# ATmega128RFA1-DevBoard.net
KiCad netlist of a schematic drawn in EAGLE
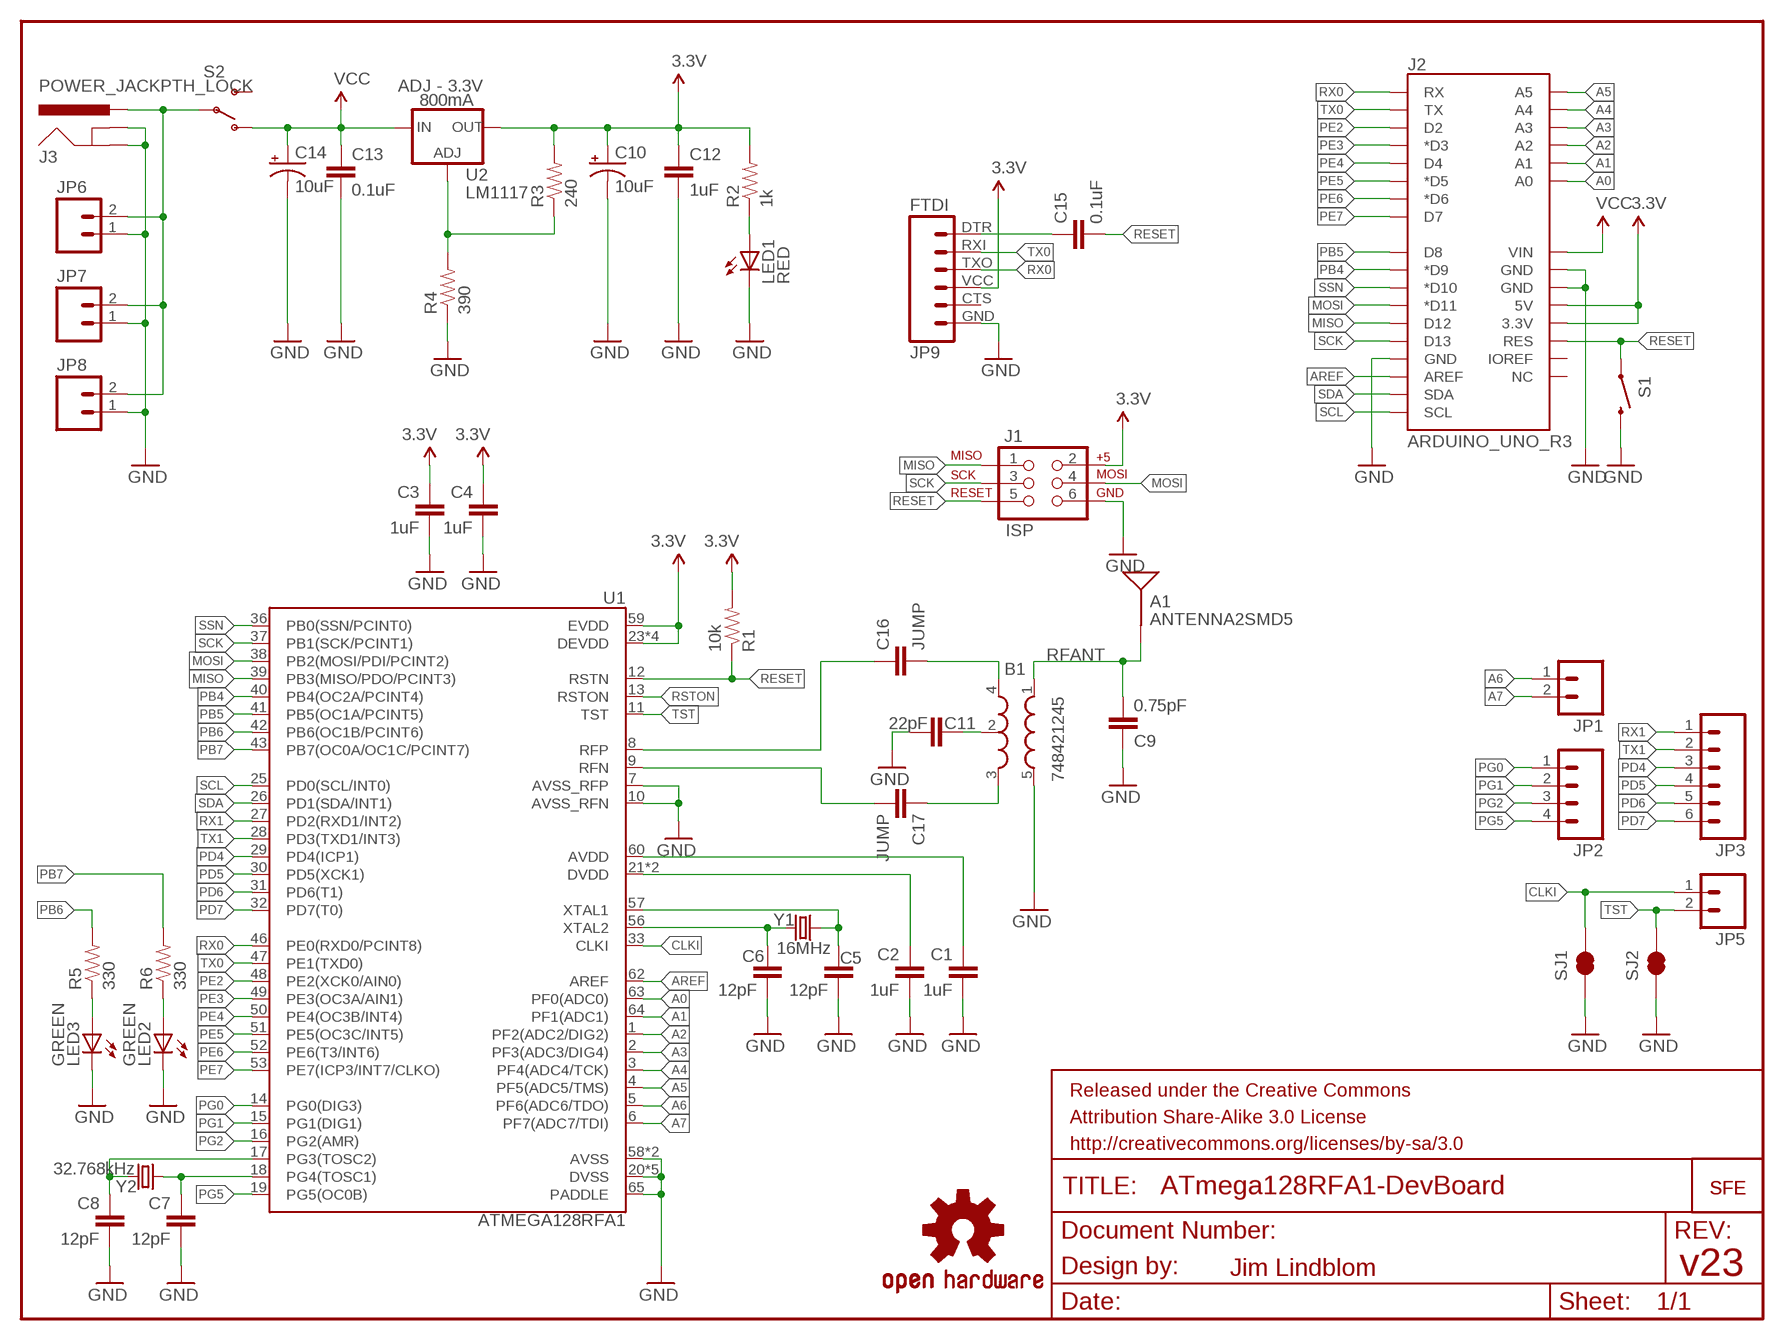
[diagram p0: schematic, sheet 1]

(export (version "E")
  (design (tool "Eeschema 10.0.6"))
  (components
    (comp (ref "A1")
      (value "ANTENNA2SMD5")
      (footprint "eagle-import:ANTENNA-CHIP5")
      (libsource (lib "eagle-import") (part "ANTENNA2SMD5"))
    )
    (comp (ref "B1")
      (value "748421245")
      (footprint "eagle-import:BALUN")
      (libsource (lib "eagle-import") (part "BALUN0805"))
    )
    (comp (ref "C1")
      (value "1uF")
      (footprint "eagle-import:0402-CAP")
      (libsource (lib "eagle-import") (part "SparkFun-Passives_CAP0402-CAP"))
    )
    (comp (ref "C2")
      (value "1uF")
      (footprint "eagle-import:0402-CAP")
      (libsource (lib "eagle-import") (part "SparkFun-Passives_CAP0402-CAP"))
    )
    (comp (ref "C3")
      (value "1uF")
      (footprint "eagle-import:0402-CAP")
      (libsource (lib "eagle-import") (part "SparkFun-Passives_CAP0402-CAP"))
    )
    (comp (ref "C4")
      (value "1uF")
      (footprint "eagle-import:0402-CAP")
      (libsource (lib "eagle-import") (part "SparkFun-Passives_CAP0402-CAP"))
    )
    (comp (ref "C5")
      (value "12pF")
      (footprint "eagle-import:0402-CAP")
      (libsource (lib "eagle-import") (part "SparkFun-Passives_CAP0402-CAP"))
    )
    (comp (ref "C6")
      (value "12pF")
      (footprint "eagle-import:0402-CAP")
      (libsource (lib "eagle-import") (part "SparkFun-Passives_CAP0402-CAP"))
    )
    (comp (ref "C7")
      (value "12pF")
      (footprint "eagle-import:0402-CAP")
      (libsource (lib "eagle-import") (part "SparkFun-Passives_CAP0402-CAP"))
    )
    (comp (ref "C8")
      (value "12pF")
      (footprint "eagle-import:0402-CAP")
      (libsource (lib "eagle-import") (part "SparkFun-Passives_CAP0402-CAP"))
    )
    (comp (ref "C9")
      (value "0.75pF")
      (footprint "eagle-import:0402-CAP")
      (libsource (lib "eagle-import") (part "SparkFun-Passives_CAP0402-CAP"))
    )
    (comp (ref "C10")
      (value "10uF")
      (footprint "eagle-import:EIA3216")
      (libsource (lib "eagle-import") (part "CAP_POL1206"))
    )
    (comp (ref "C11")
      (value "22pF")
      (footprint "eagle-import:0402-CAP")
      (libsource (lib "eagle-import") (part "SparkFun-Passives_CAP0402-CAP"))
    )
    (comp (ref "C12")
      (value "1uF")
      (footprint "eagle-import:0402-CAP")
      (libsource (lib "eagle-import") (part "SparkFun-Passives_CAP0402-CAP"))
    )
    (comp (ref "C13")
      (value "0.1uF")
      (footprint "eagle-import:0402-CAP")
      (libsource (lib "eagle-import") (part "SparkFun-Passives_CAP0402-CAP"))
    )
    (comp (ref "C14")
      (value "10uF")
      (footprint "eagle-import:EIA3216")
      (libsource (lib "eagle-import") (part "CAP_POL1206"))
    )
    (comp (ref "C15")
      (value "0.1uF")
      (footprint "eagle-import:0402-CAP")
      (libsource (lib "eagle-import") (part "SparkFun-Passives_CAP0402-CAP"))
    )
    (comp (ref "C16")
      (value "JUMP")
      (footprint "eagle-import:0402-CAP")
      (libsource (lib "eagle-import") (part "CAP0402-CAP"))
    )
    (comp (ref "C17")
      (value "JUMP")
      (footprint "eagle-import:0402-CAP")
      (libsource (lib "eagle-import") (part "CAP0402-CAP"))
    )
    (comp (ref "J1")
      (value "ISP")
      (footprint "eagle-import:2X3-NS")
      (libsource (lib "eagle-import") (part "AVR_SPI_PRG_6NS"))
    )
    (comp (ref "J2")
      (value "ARDUINO_UNO_R3")
      (footprint "eagle-import:ARDUINO_UNO_R3")
      (libsource (lib "eagle-import") (part "ARDUINO_UNO_R3"))
    )
    (comp (ref "J3")
      (value "POWER_JACKPTH_LOCK")
      (footprint "eagle-import:POWER_JACK_PTH_LOCK")
      (libsource (lib "eagle-import") (part "POWER_JACKPTH_LOCK"))
    )
    (comp (ref "JP1")
      (value "M021X02_NO_SILK")
      (footprint "eagle-import:1X02_NO_SILK")
      (libsource (lib "eagle-import") (part "M021X02_NO_SILK"))
    )
    (comp (ref "JP2")
      (value "M041X04_NO_SILK")
      (footprint "eagle-import:1X04_NO_SILK")
      (libsource (lib "eagle-import") (part "M041X04_NO_SILK"))
    )
    (comp (ref "JP3")
      (value "M06SIP-NS")
      (footprint "eagle-import:1X06_NS")
      (libsource (lib "eagle-import") (part "M06SIP-NS"))
    )
    (comp (ref "JP4")
      (value "LOGO-SFENEW")
      (footprint "eagle-import:SFE-NEW-WEBLOGO")
      (libsource (lib "eagle-import") (part "LOGO-SFENEW"))
    )
    (comp (ref "JP5")
      (value "M021X02_NO_SILK")
      (footprint "eagle-import:1X02_NO_SILK")
      (libsource (lib "eagle-import") (part "M021X02_NO_SILK"))
    )
    (comp (ref "JP6")
      (value "M02JST-PTH-2")
      (footprint "eagle-import:JST-2-PTH")
      (libsource (lib "eagle-import") (part "M02JST-PTH-2"))
    )
    (comp (ref "JP7")
      (value "M021X02_NO_SILK")
      (footprint "eagle-import:1X02_NO_SILK")
      (libsource (lib "eagle-import") (part "M021X02_NO_SILK"))
    )
    (comp (ref "JP8")
      (value "M023.5MM-NO_SILK")
      (footprint "eagle-import:SCREWTERMINAL-3.5MM-2-NS")
      (libsource (lib "eagle-import") (part "M023.5MM-NO_SILK"))
    )
    (comp (ref "JP9")
      (value "FTDI")
      (footprint "eagle-import:FTDI_BASIC")
      (libsource (lib "eagle-import") (part "FTDI_BASICPTH"))
    )
    (comp (ref "JP10")
      (value "LOGO-SFENEW")
      (footprint "eagle-import:SFE-NEW-WEBLOGO")
      (libsource (lib "eagle-import") (part "LOGO-SFENEW"))
    )
    (comp (ref "LED1")
      (value "RED")
      (footprint "eagle-import:LED-0603")
      (libsource (lib "eagle-import") (part "LED0603"))
    )
    (comp (ref "LED2")
      (value "GREEN")
      (footprint "eagle-import:LED-0603")
      (libsource (lib "eagle-import") (part "LED0603"))
    )
    (comp (ref "LED3")
      (value "GREEN")
      (footprint "eagle-import:LED-0603")
      (libsource (lib "eagle-import") (part "LED0603"))
    )
    (comp (ref "R1")
      (value "10k")
      (footprint "eagle-import:0402-RES")
      (libsource (lib "eagle-import") (part "SparkFun-Passives_RESISTOR0402-RES"))
    )
    (comp (ref "R2")
      (value "1k")
      (footprint "eagle-import:0402-RES")
      (libsource (lib "eagle-import") (part "SparkFun-Passives_RESISTOR0402-RES"))
    )
    (comp (ref "R3")
      (value "240")
      (footprint "eagle-import:0402-RES")
      (libsource (lib "eagle-import") (part "RESISTOR0402-RES"))
    )
    (comp (ref "R4")
      (value "390")
      (footprint "eagle-import:0402-RES")
      (libsource (lib "eagle-import") (part "RESISTOR0402-RES"))
    )
    (comp (ref "R5")
      (value "330")
      (footprint "eagle-import:0402-RES")
      (libsource (lib "eagle-import") (part "RESISTOR0402-RES"))
    )
    (comp (ref "R6")
      (value "330")
      (footprint "eagle-import:0402-RES")
      (libsource (lib "eagle-import") (part "RESISTOR0402-RES"))
    )
    (comp (ref "S1")
      (value "SWITCH-MOMENTARY-2SMD")
      (footprint "eagle-import:TACTILE_SWITCH_SMD")
      (libsource (lib "eagle-import") (part "SWITCH-MOMENTARY-2SMD"))
    )
    (comp (ref "S2")
      (value "SWITCH-SPST-SMD-A")
      (footprint "eagle-import:SWITCH-SPST-SMD-A")
      (libsource (lib "eagle-import") (part "SWITCH-SPST-SMD-A"))
    )
    (comp (ref "SJ1")
      (value "SOLDERJUMPERTRACE")
      (footprint "eagle-import:SJ_2S-TRACE")
      (libsource (lib "eagle-import") (part "SOLDERJUMPERTRACE"))
    )
    (comp (ref "SJ2")
      (value "SOLDERJUMPERTRACE")
      (footprint "eagle-import:SJ_2S-TRACE")
      (libsource (lib "eagle-import") (part "SOLDERJUMPERTRACE"))
    )
    (comp (ref "U$1")
      (value "OSHW-LOGOS")
      (footprint "eagle-import:OSHW-LOGO-S")
      (libsource (lib "eagle-import") (part "OSHW-LOGOS"))
    )
    (comp (ref "U1")
      (value "ATMEGA128RFA1")
      (footprint "eagle-import:QFN-64")
      (libsource (lib "eagle-import") (part "ATMEGA128RFA1"))
    )
    (comp (ref "U2")
      (value "LM1117")
      (footprint "eagle-import:SOT223")
      (libsource (lib "eagle-import") (part "V_REG_317SMD"))
    )
    (comp (ref "Y1")
      (value "16MHz")
      (footprint "eagle-import:CRYSTAL-SMD-5X3")
      (libsource (lib "eagle-import") (part "CRYSTAL5X3"))
    )
    (comp (ref "Y2")
      (value "32.768kHz")
      (footprint "eagle-import:CRYSTAL-32KHZ-SMD")
      (libsource (lib "eagle-import") (part "CRYSTAL32-SMD"))
    )
  )
  (nets
    (net (code "1") (name "/RFANT") (class "Default")
      (node (ref "A1") (pin "FEED") (pinfunction "SIGNAL_FEED") (pintype "bidirectional"))
      (node (ref "B1") (pin "1") (pinfunction "IN_1") (pintype "bidirectional"))
      (node (ref "C9") (pin "2") (pinfunction "2_2") (pintype "passive"))
    )
    (net (code "2") (name "3.3V") (class "Default")
      (node (ref "C10") (pin "A") (pinfunction "+_A") (pintype "passive"))
      (node (ref "C12") (pin "1") (pinfunction "1_1") (pintype "passive"))
      (node (ref "C3") (pin "1") (pinfunction "1_1") (pintype "passive"))
      (node (ref "C4") (pin "1") (pinfunction "1_1") (pintype "passive"))
      (node (ref "J1") (pin "2") (pinfunction "2_2") (pintype "passive"))
      (node (ref "J2") (pin "3.3V") (pinfunction "3.3V_3.3V") (pintype "bidirectional"))
      (node (ref "J2") (pin "5V") (pinfunction "5V_5V") (pintype "bidirectional"))
      (node (ref "JP9") (pin "VCC") (pinfunction "4_VCC") (pintype "passive"))
      (node (ref "R1") (pin "2") (pinfunction "2_2") (pintype "passive"))
      (node (ref "R2") (pin "2") (pinfunction "2_2") (pintype "passive"))
      (node (ref "R3") (pin "2") (pinfunction "2_2") (pintype "passive"))
      (node (ref "U1") (pin "23") (pinfunction "DEVDD_23") (pintype "bidirectional"))
      (node (ref "U1") (pin "34") (pinfunction "DEVDD_34") (pintype "bidirectional"))
      (node (ref "U1") (pin "44") (pinfunction "DEVDD_44") (pintype "bidirectional"))
      (node (ref "U1") (pin "54") (pinfunction "DEVDD_54") (pintype "bidirectional"))
      (node (ref "U1") (pin "59") (pinfunction "EVDD_59") (pintype "bidirectional"))
      (node (ref "U2") (pin "2") (pinfunction "OUT_2") (pintype "output"))
    )
    (net (code "3") (name "A0") (class "Default")
      (node (ref "J2") (pin "A0") (pinfunction "A0_A0") (pintype "bidirectional"))
      (node (ref "U1") (pin "63") (pinfunction "PF0(ADC0)_63") (pintype "bidirectional"))
    )
    (net (code "4") (name "A1") (class "Default")
      (node (ref "J2") (pin "A1") (pinfunction "A1_A1") (pintype "bidirectional"))
      (node (ref "U1") (pin "64") (pinfunction "PF1(ADC1)_64") (pintype "bidirectional"))
    )
    (net (code "5") (name "A2") (class "Default")
      (node (ref "J2") (pin "A2") (pinfunction "A2_A2") (pintype "bidirectional"))
      (node (ref "U1") (pin "1") (pinfunction "PF2(ADC2/DIG2)_1") (pintype "bidirectional"))
    )
    (net (code "6") (name "A3") (class "Default")
      (node (ref "J2") (pin "A3") (pinfunction "A3_A3") (pintype "bidirectional"))
      (node (ref "U1") (pin "2") (pinfunction "PF3(ADC3/DIG4)_2") (pintype "bidirectional"))
    )
    (net (code "7") (name "A4") (class "Default")
      (node (ref "J2") (pin "A4") (pinfunction "A4_A4") (pintype "bidirectional"))
      (node (ref "U1") (pin "3") (pinfunction "PF4(ADC4/TCK)_3") (pintype "bidirectional"))
    )
    (net (code "8") (name "A5") (class "Default")
      (node (ref "J2") (pin "A5") (pinfunction "A5_A5") (pintype "bidirectional"))
      (node (ref "U1") (pin "4") (pinfunction "PF5(ADC5/TMS)_4") (pintype "bidirectional"))
    )
    (net (code "9") (name "A6") (class "Default")
      (node (ref "JP1") (pin "1") (pinfunction "1_1") (pintype "passive"))
      (node (ref "U1") (pin "5") (pinfunction "PF6(ADC6/TDO)_5") (pintype "bidirectional"))
    )
    (net (code "10") (name "A7") (class "Default")
      (node (ref "JP1") (pin "2") (pinfunction "2_2") (pintype "passive"))
      (node (ref "U1") (pin "6") (pinfunction "PF7(ADC7/TDI)_6") (pintype "bidirectional"))
    )
    (net (code "11") (name "AREF") (class "Default")
      (node (ref "J2") (pin "AREF") (pinfunction "AREF_AREF") (pintype "bidirectional"))
      (node (ref "U1") (pin "62") (pinfunction "AREF_62") (pintype "bidirectional"))
    )
    (net (code "12") (name "CLKI") (class "Default")
      (node (ref "JP5") (pin "1") (pinfunction "1_1") (pintype "passive"))
      (node (ref "SJ1") (pin "2") (pinfunction "2_2") (pintype "passive"))
      (node (ref "U1") (pin "33") (pinfunction "CLKI_33") (pintype "bidirectional"))
    )
    (net (code "13") (name "GND") (class "Default")
      (node (ref "B1") (pin "5") (pinfunction "GND_5") (pintype "bidirectional"))
      (node (ref "C1") (pin "2") (pinfunction "2_2") (pintype "passive"))
      (node (ref "C10") (pin "C") (pinfunction "-_C") (pintype "passive"))
      (node (ref "C11") (pin "2") (pinfunction "2_2") (pintype "passive"))
      (node (ref "C12") (pin "2") (pinfunction "2_2") (pintype "passive"))
      (node (ref "C13") (pin "2") (pinfunction "2_2") (pintype "passive"))
      (node (ref "C14") (pin "C") (pinfunction "-_C") (pintype "passive"))
      (node (ref "C2") (pin "2") (pinfunction "2_2") (pintype "passive"))
      (node (ref "C3") (pin "2") (pinfunction "2_2") (pintype "passive"))
      (node (ref "C4") (pin "2") (pinfunction "2_2") (pintype "passive"))
      (node (ref "C5") (pin "2") (pinfunction "2_2") (pintype "passive"))
      (node (ref "C6") (pin "2") (pinfunction "2_2") (pintype "passive"))
      (node (ref "C7") (pin "2") (pinfunction "2_2") (pintype "passive"))
      (node (ref "C8") (pin "2") (pinfunction "2_2") (pintype "passive"))
      (node (ref "C9") (pin "1") (pinfunction "1_1") (pintype "passive"))
      (node (ref "J1") (pin "6") (pinfunction "6_6") (pintype "passive"))
      (node (ref "J2") (pin "GND@0") (pinfunction "GND_GND@0") (pintype "bidirectional"))
      (node (ref "J2") (pin "GND@1") (pinfunction "GND_GND@1") (pintype "bidirectional"))
      (node (ref "J2") (pin "GND@2") (pinfunction "GND_GND@2") (pintype "bidirectional"))
      (node (ref "J3") (pin "GND") (pinfunction "GND_GND") (pintype "bidirectional"))
      (node (ref "J3") (pin "GNDBREAK") (pinfunction "GNDBREAK_GNDBREAK") (pintype "bidirectional"))
      (node (ref "JP6") (pin "1") (pinfunction "1_1") (pintype "passive"))
      (node (ref "JP7") (pin "1") (pinfunction "1_1") (pintype "passive"))
      (node (ref "JP8") (pin "1") (pinfunction "1_1") (pintype "passive"))
      (node (ref "JP9") (pin "GND") (pinfunction "6_GND") (pintype "passive"))
      (node (ref "LED1") (pin "C") (pinfunction "C_C") (pintype "passive"))
      (node (ref "LED2") (pin "C") (pinfunction "C_C") (pintype "passive"))
      (node (ref "LED3") (pin "C") (pinfunction "C_C") (pintype "passive"))
      (node (ref "R4") (pin "1") (pinfunction "1_1") (pintype "passive"))
      (node (ref "S1") (pin "3") (pinfunction "2_3") (pintype "passive"))
      (node (ref "SJ1") (pin "1") (pinfunction "1_1") (pintype "passive"))
      (node (ref "SJ2") (pin "1") (pinfunction "1_1") (pintype "passive"))
      (node (ref "U1") (pin "10") (pinfunction "AVSS_RFN_10") (pintype "bidirectional"))
      (node (ref "U1") (pin "20") (pinfunction "DVSS_20") (pintype "bidirectional"))
      (node (ref "U1") (pin "24") (pinfunction "DVSS_24") (pintype "bidirectional"))
      (node (ref "U1") (pin "35") (pinfunction "DVSS_35") (pintype "bidirectional"))
      (node (ref "U1") (pin "45") (pinfunction "DVSS_45") (pintype "bidirectional"))
      (node (ref "U1") (pin "55") (pinfunction "DVSS_55") (pintype "bidirectional"))
      (node (ref "U1") (pin "58") (pinfunction "AVSS_58") (pintype "bidirectional"))
      (node (ref "U1") (pin "61") (pinfunction "AVSS_61") (pintype "bidirectional"))
      (node (ref "U1") (pin "65") (pinfunction "PADDLE_65") (pintype "bidirectional"))
      (node (ref "U1") (pin "7") (pinfunction "AVSS_RFP_7") (pintype "bidirectional"))
    )
    (net (code "14") (name "MISO") (class "Default")
      (node (ref "J1") (pin "1") (pinfunction "1_1") (pintype "passive"))
      (node (ref "J2") (pin "D12") (pinfunction "D12_D12") (pintype "bidirectional"))
      (node (ref "U1") (pin "39") (pinfunction "PB3(MISO/PDO/PCINT3)_39") (pintype "bidirectional"))
    )
    (net (code "15") (name "MOSI") (class "Default")
      (node (ref "J1") (pin "4") (pinfunction "4_4") (pintype "passive"))
      (node (ref "J2") (pin "D11") (pinfunction "*D11_D11") (pintype "bidirectional"))
      (node (ref "U1") (pin "38") (pinfunction "PB2(MOSI/PDI/PCINT2)_38") (pintype "bidirectional"))
    )
    (net (code "16") (name "Net-(B1-GND-Pad2)") (class "Default")
      (node (ref "B1") (pin "2") (pinfunction "GND_2") (pintype "bidirectional"))
      (node (ref "C11") (pin "1") (pinfunction "1_1") (pintype "passive"))
    )
    (net (code "17") (name "Net-(B1-OUT1)") (class "Default")
      (node (ref "B1") (pin "4") (pinfunction "OUT1_4") (pintype "bidirectional"))
      (node (ref "C16") (pin "2") (pinfunction "2_2") (pintype "passive"))
    )
    (net (code "18") (name "Net-(B1-OUT2)") (class "Default")
      (node (ref "B1") (pin "3") (pinfunction "OUT2_3") (pintype "bidirectional"))
      (node (ref "C17") (pin "1") (pinfunction "1_1") (pintype "passive"))
    )
    (net (code "19") (name "Net-(C2-Pad1)") (class "Default")
      (node (ref "C2") (pin "1") (pinfunction "1_1") (pintype "passive"))
      (node (ref "U1") (pin "21") (pinfunction "DVDD_21") (pintype "bidirectional"))
      (node (ref "U1") (pin "22") (pinfunction "DVDD_22") (pintype "bidirectional"))
    )
    (net (code "20") (name "Net-(JP9-1)") (class "Default")
      (node (ref "C15") (pin "1") (pinfunction "1_1") (pintype "passive"))
      (node (ref "JP9") (pin "DTR") (pinfunction "1_DTR") (pintype "passive"))
    )
    (net (code "21") (name "Net-(LED1-PadA)") (class "Default")
      (node (ref "LED1") (pin "A") (pinfunction "A_A") (pintype "passive"))
      (node (ref "R2") (pin "1") (pinfunction "1_1") (pintype "passive"))
    )
    (net (code "22") (name "Net-(LED2-PadA)") (class "Default")
      (node (ref "LED2") (pin "A") (pinfunction "A_A") (pintype "passive"))
      (node (ref "R6") (pin "1") (pinfunction "1_1") (pintype "passive"))
    )
    (net (code "23") (name "Net-(LED3-PadA)") (class "Default")
      (node (ref "LED3") (pin "A") (pinfunction "A_A") (pintype "passive"))
      (node (ref "R5") (pin "1") (pinfunction "1_1") (pintype "passive"))
    )
    (net (code "24") (name "Net-(S2-P)") (class "Default")
      (node (ref "J3") (pin "PWR") (pinfunction "PWR_PWR") (pintype "bidirectional"))
      (node (ref "JP6") (pin "2") (pinfunction "2_2") (pintype "passive"))
      (node (ref "JP7") (pin "2") (pinfunction "2_2") (pintype "passive"))
      (node (ref "JP8") (pin "2") (pinfunction "2_2") (pintype "passive"))
      (node (ref "S2") (pin "2") (pinfunction "P_2") (pintype "passive"))
    )
    (net (code "25") (name "Net-(U1-AVDD)") (class "Default")
      (node (ref "C1") (pin "1") (pinfunction "1_1") (pintype "passive"))
      (node (ref "U1") (pin "60") (pinfunction "AVDD_60") (pintype "bidirectional"))
    )
    (net (code "26") (name "Net-(U1-PG3(TOSC2))") (class "Default")
      (node (ref "C8") (pin "1") (pinfunction "1_1") (pintype "passive"))
      (node (ref "U1") (pin "17") (pinfunction "PG3(TOSC2)_17") (pintype "bidirectional"))
      (node (ref "Y2") (pin "X2") (pinfunction "2_X2") (pintype "passive"))
    )
    (net (code "27") (name "Net-(U1-PG4(TOSC1))") (class "Default")
      (node (ref "C7") (pin "1") (pinfunction "1_1") (pintype "passive"))
      (node (ref "U1") (pin "18") (pinfunction "PG4(TOSC1)_18") (pintype "bidirectional"))
      (node (ref "Y2") (pin "X1") (pinfunction "1_X1") (pintype "passive"))
    )
    (net (code "28") (name "Net-(U1-RFN)") (class "Default")
      (node (ref "C17") (pin "2") (pinfunction "2_2") (pintype "passive"))
      (node (ref "U1") (pin "9") (pinfunction "RFN_9") (pintype "bidirectional"))
    )
    (net (code "29") (name "Net-(U1-RFP)") (class "Default")
      (node (ref "C16") (pin "1") (pinfunction "1_1") (pintype "passive"))
      (node (ref "U1") (pin "8") (pinfunction "RFP_8") (pintype "bidirectional"))
    )
    (net (code "30") (name "Net-(U1-XTAL1)") (class "Default")
      (node (ref "C5") (pin "1") (pinfunction "1_1") (pintype "passive"))
      (node (ref "U1") (pin "57") (pinfunction "XTAL1_57") (pintype "bidirectional"))
      (node (ref "Y1") (pin "3") (pinfunction "2_3") (pintype "passive"))
    )
    (net (code "31") (name "Net-(U1-XTAL2)") (class "Default")
      (node (ref "C6") (pin "1") (pinfunction "1_1") (pintype "passive"))
      (node (ref "U1") (pin "56") (pinfunction "XTAL2_56") (pintype "bidirectional"))
      (node (ref "Y1") (pin "1") (pinfunction "1_1") (pintype "passive"))
    )
    (net (code "32") (name "Net-(U2-ADJ)") (class "Default")
      (node (ref "R3") (pin "1") (pinfunction "1_1") (pintype "passive"))
      (node (ref "R4") (pin "2") (pinfunction "2_2") (pintype "passive"))
      (node (ref "U2") (pin "1") (pinfunction "ADJ_1") (pintype "input"))
    )
    (net (code "33") (name "PB4") (class "Default")
      (node (ref "J2") (pin "D9") (pinfunction "*D9_D9") (pintype "bidirectional"))
      (node (ref "U1") (pin "40") (pinfunction "PB4(OC2A/PCINT4)_40") (pintype "bidirectional"))
    )
    (net (code "34") (name "PB5") (class "Default")
      (node (ref "J2") (pin "D8") (pinfunction "D8_D8") (pintype "bidirectional"))
      (node (ref "U1") (pin "41") (pinfunction "PB5(OC1A/PCINT5)_41") (pintype "bidirectional"))
    )
    (net (code "35") (name "PB6") (class "Default")
      (node (ref "R5") (pin "2") (pinfunction "2_2") (pintype "passive"))
      (node (ref "U1") (pin "42") (pinfunction "PB6(OC1B/PCINT6)_42") (pintype "bidirectional"))
    )
    (net (code "36") (name "PB7") (class "Default")
      (node (ref "R6") (pin "2") (pinfunction "2_2") (pintype "passive"))
      (node (ref "U1") (pin "43") (pinfunction "PB7(OC0A/OC1C/PCINT7)_43") (pintype "bidirectional"))
    )
    (net (code "37") (name "PD4") (class "Default")
      (node (ref "JP3") (pin "3") (pinfunction "3_3") (pintype "passive"))
      (node (ref "U1") (pin "29") (pinfunction "PD4(ICP1)_29") (pintype "bidirectional"))
    )
    (net (code "38") (name "PD5") (class "Default")
      (node (ref "JP3") (pin "4") (pinfunction "4_4") (pintype "passive"))
      (node (ref "U1") (pin "30") (pinfunction "PD5(XCK1)_30") (pintype "bidirectional"))
    )
    (net (code "39") (name "PD6") (class "Default")
      (node (ref "JP3") (pin "5") (pinfunction "5_5") (pintype "passive"))
      (node (ref "U1") (pin "31") (pinfunction "PD6(T1)_31") (pintype "bidirectional"))
    )
    (net (code "40") (name "PD7") (class "Default")
      (node (ref "JP3") (pin "6") (pinfunction "6_6") (pintype "passive"))
      (node (ref "U1") (pin "32") (pinfunction "PD7(T0)_32") (pintype "bidirectional"))
    )
    (net (code "41") (name "PE2") (class "Default")
      (node (ref "J2") (pin "D2") (pinfunction "D2_D2") (pintype "bidirectional"))
      (node (ref "U1") (pin "48") (pinfunction "PE2(XCK0/AIN0)_48") (pintype "bidirectional"))
    )
    (net (code "42") (name "PE3") (class "Default")
      (node (ref "J2") (pin "D3") (pinfunction "*D3_D3") (pintype "bidirectional"))
      (node (ref "U1") (pin "49") (pinfunction "PE3(OC3A/AIN1)_49") (pintype "bidirectional"))
    )
    (net (code "43") (name "PE4") (class "Default")
      (node (ref "J2") (pin "D4") (pinfunction "D4_D4") (pintype "bidirectional"))
      (node (ref "U1") (pin "50") (pinfunction "PE4(OC3B/INT4)_50") (pintype "bidirectional"))
    )
    (net (code "44") (name "PE5") (class "Default")
      (node (ref "J2") (pin "D5") (pinfunction "*D5_D5") (pintype "bidirectional"))
      (node (ref "U1") (pin "51") (pinfunction "PE5(OC3C/INT5)_51") (pintype "bidirectional"))
    )
    (net (code "45") (name "PE6") (class "Default")
      (node (ref "J2") (pin "D6") (pinfunction "*D6_D6") (pintype "bidirectional"))
      (node (ref "U1") (pin "52") (pinfunction "PE6(T3/INT6)_52") (pintype "bidirectional"))
    )
    (net (code "46") (name "PE7") (class "Default")
      (node (ref "J2") (pin "D7") (pinfunction "D7_D7") (pintype "bidirectional"))
      (node (ref "U1") (pin "53") (pinfunction "PE7(ICP3/INT7/CLKO)_53") (pintype "bidirectional"))
    )
    (net (code "47") (name "PG0") (class "Default")
      (node (ref "JP2") (pin "1") (pinfunction "1_1") (pintype "passive"))
      (node (ref "U1") (pin "14") (pinfunction "PG0(DIG3)_14") (pintype "bidirectional"))
    )
    (net (code "48") (name "PG1") (class "Default")
      (node (ref "JP2") (pin "2") (pinfunction "2_2") (pintype "passive"))
      (node (ref "U1") (pin "15") (pinfunction "PG1(DIG1)_15") (pintype "bidirectional"))
    )
    (net (code "49") (name "PG2") (class "Default")
      (node (ref "JP2") (pin "3") (pinfunction "3_3") (pintype "passive"))
      (node (ref "U1") (pin "16") (pinfunction "PG2(AMR)_16") (pintype "bidirectional"))
    )
    (net (code "50") (name "PG5") (class "Default")
      (node (ref "JP2") (pin "4") (pinfunction "4_4") (pintype "passive"))
      (node (ref "U1") (pin "19") (pinfunction "PG5(OC0B)_19") (pintype "bidirectional"))
    )
    (net (code "51") (name "RESET") (class "Default")
      (node (ref "C15") (pin "2") (pinfunction "2_2") (pintype "passive"))
      (node (ref "J1") (pin "5") (pinfunction "5_5") (pintype "passive"))
      (node (ref "J2") (pin "RES") (pinfunction "RES_RES") (pintype "bidirectional"))
      (node (ref "R1") (pin "1") (pinfunction "1_1") (pintype "passive"))
      (node (ref "S1") (pin "1") (pinfunction "1_1") (pintype "passive"))
      (node (ref "U1") (pin "12") (pinfunction "RSTN_12") (pintype "bidirectional"))
    )
    (net (code "52") (name "RSTON") (class "Default")
      (node (ref "U1") (pin "13") (pinfunction "RSTON_13") (pintype "bidirectional"))
    )
    (net (code "53") (name "RX0") (class "Default")
      (node (ref "J2") (pin "RX") (pinfunction "RX_RX") (pintype "bidirectional"))
      (node (ref "JP9") (pin "TXO") (pinfunction "3_TXO") (pintype "passive"))
      (node (ref "U1") (pin "46") (pinfunction "PE0(RXD0/PCINT8)_46") (pintype "bidirectional"))
    )
    (net (code "54") (name "RX1") (class "Default")
      (node (ref "JP3") (pin "1") (pinfunction "1_1") (pintype "passive"))
      (node (ref "U1") (pin "27") (pinfunction "PD2(RXD1/INT2)_27") (pintype "bidirectional"))
    )
    (net (code "55") (name "SCK") (class "Default")
      (node (ref "J1") (pin "3") (pinfunction "3_3") (pintype "passive"))
      (node (ref "J2") (pin "D13") (pinfunction "D13_D13") (pintype "bidirectional"))
      (node (ref "U1") (pin "37") (pinfunction "PB1(SCK/PCINT1)_37") (pintype "bidirectional"))
    )
    (net (code "56") (name "SCL") (class "Default")
      (node (ref "J2") (pin "SCL") (pinfunction "SCL_SCL") (pintype "bidirectional"))
      (node (ref "U1") (pin "25") (pinfunction "PD0(SCL/INT0)_25") (pintype "bidirectional"))
    )
    (net (code "57") (name "SDA") (class "Default")
      (node (ref "J2") (pin "SDA") (pinfunction "SDA_SDA") (pintype "bidirectional"))
      (node (ref "U1") (pin "26") (pinfunction "PD1(SDA/INT1)_26") (pintype "bidirectional"))
    )
    (net (code "58") (name "SSN") (class "Default")
      (node (ref "J2") (pin "D10") (pinfunction "*D10_D10") (pintype "bidirectional"))
      (node (ref "U1") (pin "36") (pinfunction "PB0(SSN/PCINT0)_36") (pintype "bidirectional"))
    )
    (net (code "59") (name "TST") (class "Default")
      (node (ref "JP5") (pin "2") (pinfunction "2_2") (pintype "passive"))
      (node (ref "SJ2") (pin "2") (pinfunction "2_2") (pintype "passive"))
      (node (ref "U1") (pin "11") (pinfunction "TST_11") (pintype "bidirectional"))
    )
    (net (code "60") (name "TX0") (class "Default")
      (node (ref "J2") (pin "TX") (pinfunction "TX_TX") (pintype "bidirectional"))
      (node (ref "JP9") (pin "RXI") (pinfunction "2_RXI") (pintype "passive"))
      (node (ref "U1") (pin "47") (pinfunction "PE1(TXD0)_47") (pintype "bidirectional"))
    )
    (net (code "61") (name "TX1") (class "Default")
      (node (ref "JP3") (pin "2") (pinfunction "2_2") (pintype "passive"))
      (node (ref "U1") (pin "28") (pinfunction "PD3(TXD1/INT3)_28") (pintype "bidirectional"))
    )
    (net (code "62") (name "VCC") (class "Default")
      (node (ref "C13") (pin "1") (pinfunction "1_1") (pintype "passive"))
      (node (ref "C14") (pin "A") (pinfunction "+_A") (pintype "passive"))
      (node (ref "J2") (pin "VIN") (pinfunction "VIN_VIN") (pintype "bidirectional"))
      (node (ref "S2") (pin "1") (pinfunction "O_1") (pintype "passive"))
      (node (ref "U2") (pin "3") (pinfunction "IN_3") (pintype "input"))
    )
    (net (code "63") (name "unconnected-(J2-PadIOREF)") (class "Default")
      (node (ref "J2") (pin "IOREF") (pinfunction "IOREF_IOREF") (pintype "bidirectional"))
    )
    (net (code "64") (name "unconnected-(J2-PadNC)") (class "Default")
      (node (ref "J2") (pin "NC") (pinfunction "NC_NC") (pintype "bidirectional"))
    )
    (net (code "65") (name "unconnected-(JP9-5-PadCTS)") (class "Default")
      (node (ref "JP9") (pin "CTS") (pinfunction "5_CTS") (pintype "passive"))
    )
    (net (code "66") (name "unconnected-(S2-S-Pad3)") (class "Default")
      (node (ref "S2") (pin "3") (pinfunction "S_3") (pintype "passive"))
    )
  )
)
